# CPLD.net
KiCad netlist of a schematic drawn in Altium Designer
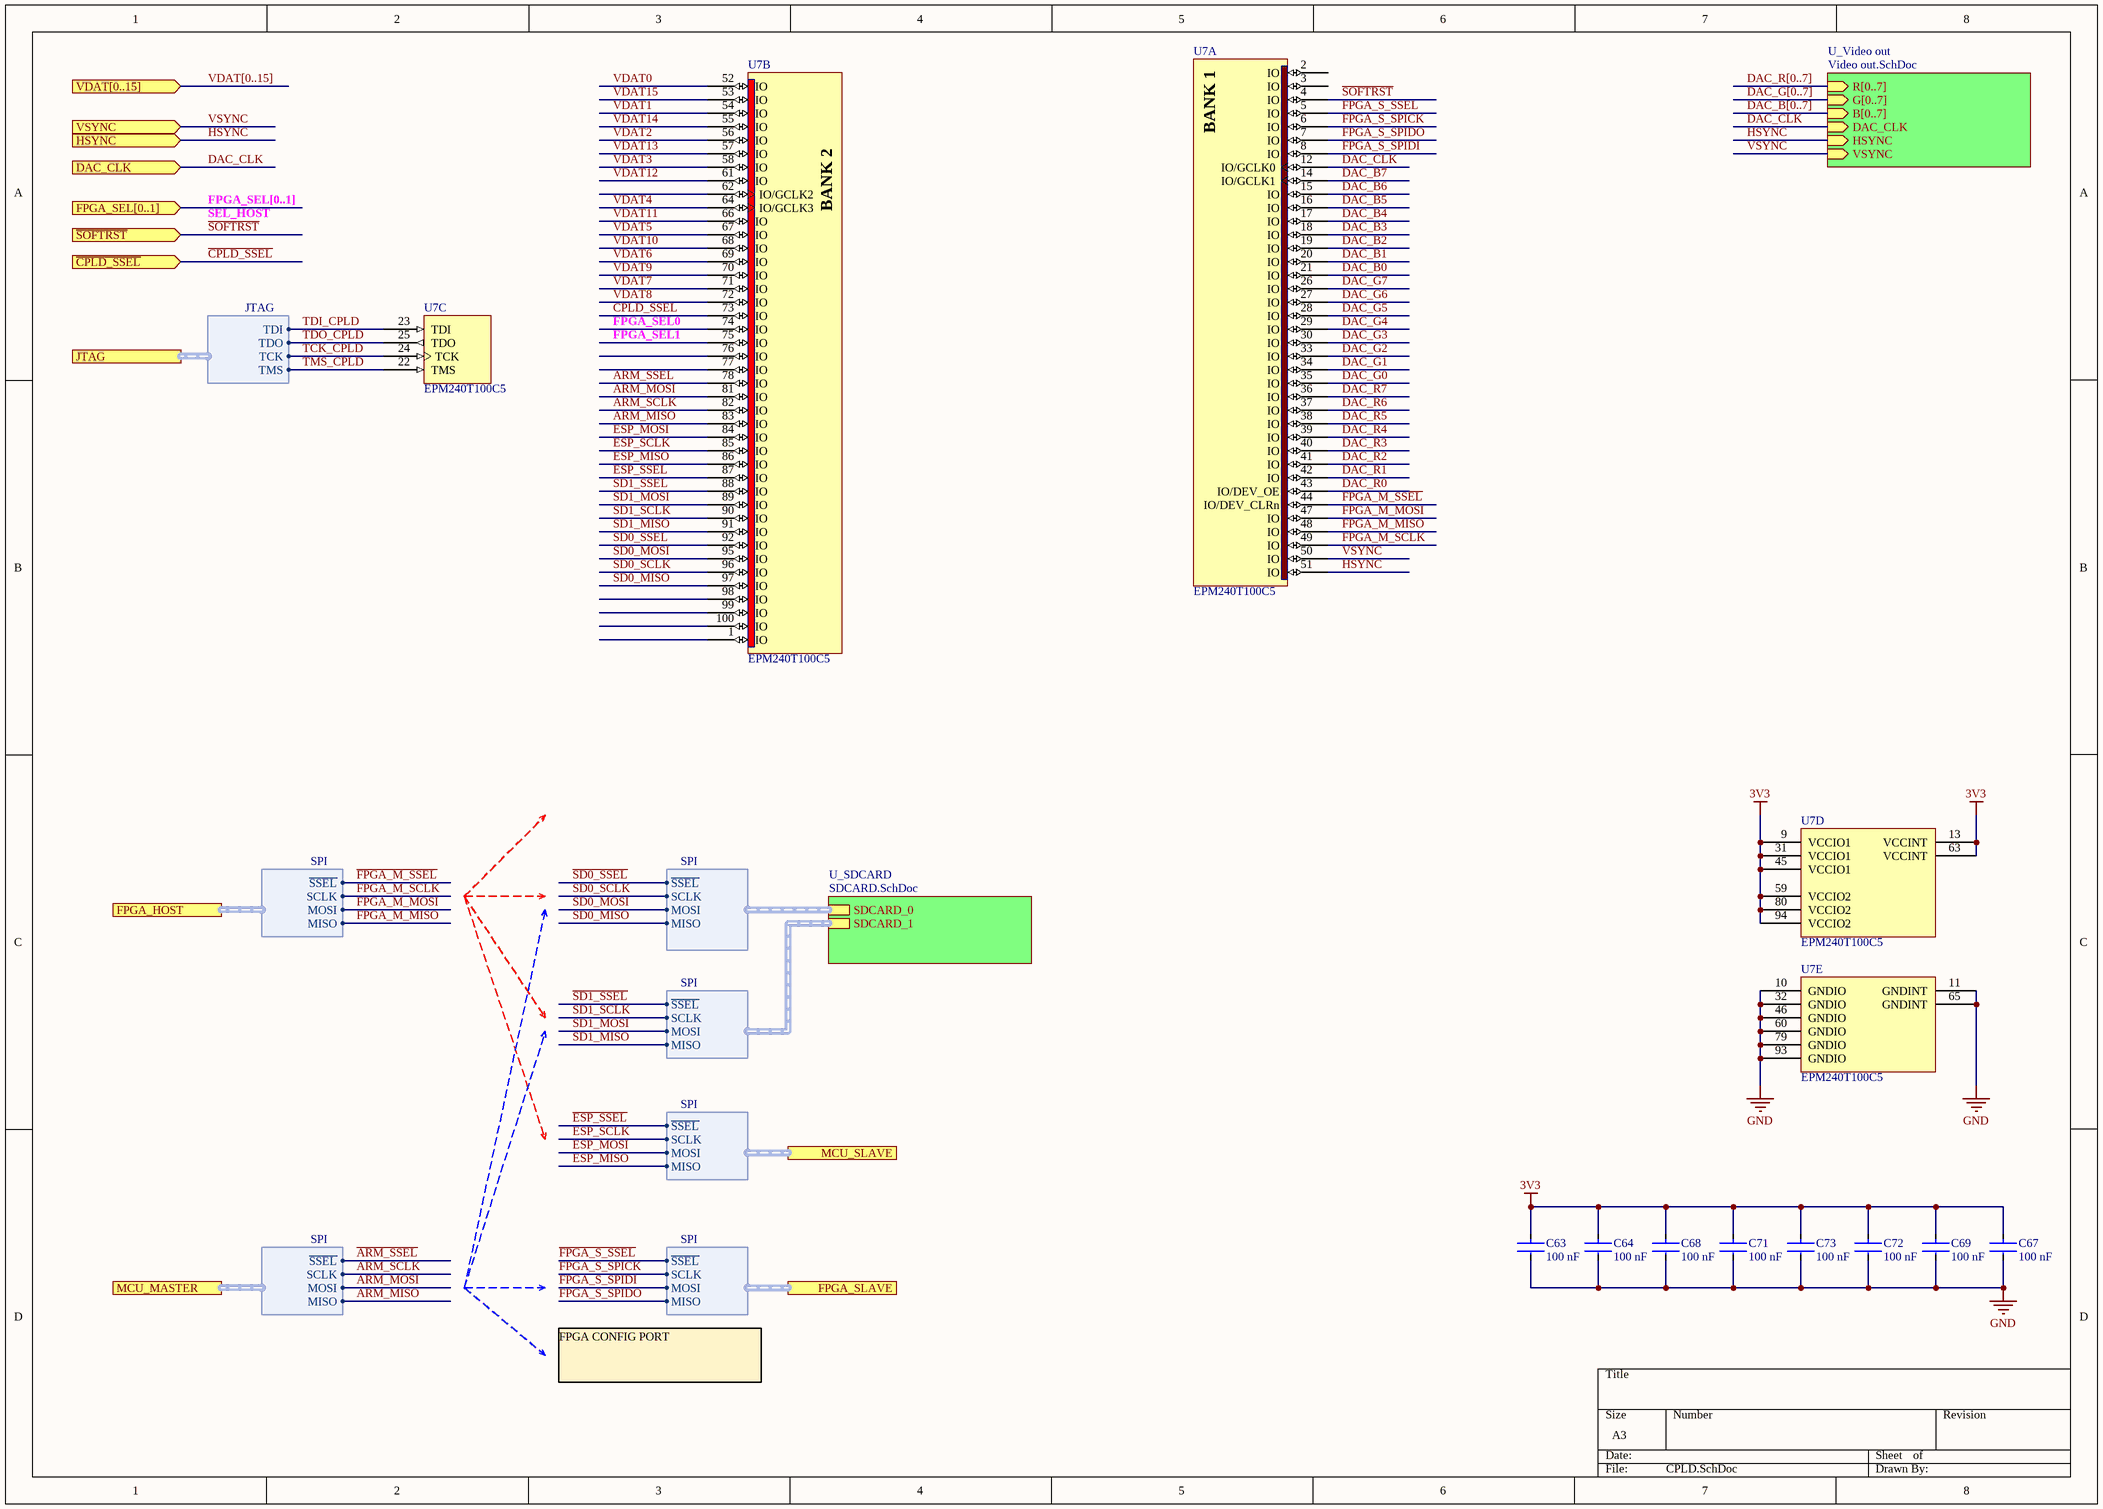
[diagram p0: CPLD.SchDoc]

(export (version "E")
  (design (tool "Eeschema 10.0.6"))
  (components
    (comp (ref "C63")
      (value "CC0805KRX7R9BB104")
      (footprint "FP-CC0805-0_85-IPC_A")
      (description "CAP CER 0.1UF 50V X7R 0805")
      (fields (field (name "MANUFACTURER") "Yageo") (field (name "CAPACITANCE") "100 nF"))
      (libsource (lib "SchLib") (part "CMP-2100-03606-3"))
    )
    (comp (ref "C64")
      (value "CC0805KRX7R9BB104")
      (footprint "FP-CC0805-0_85-IPC_A")
      (description "CAP CER 0.1UF 50V X7R 0805")
      (fields (field (name "MANUFACTURER") "Yageo") (field (name "CAPACITANCE") "100 nF"))
      (libsource (lib "SchLib") (part "CMP-2100-03606-3"))
    )
    (comp (ref "C67")
      (value "CC0805KRX7R9BB104")
      (footprint "FP-CC0805-0_85-IPC_A")
      (description "CAP CER 0.1UF 50V X7R 0805")
      (fields (field (name "MANUFACTURER") "Yageo") (field (name "CAPACITANCE") "100 nF"))
      (libsource (lib "SchLib") (part "CMP-2100-03606-3"))
    )
    (comp (ref "C68")
      (value "CC0805KRX7R9BB104")
      (footprint "FP-CC0805-0_85-IPC_A")
      (description "CAP CER 0.1UF 50V X7R 0805")
      (fields (field (name "MANUFACTURER") "Yageo") (field (name "CAPACITANCE") "100 nF"))
      (libsource (lib "SchLib") (part "CMP-2100-03606-3"))
    )
    (comp (ref "C69")
      (value "CC0805KRX7R9BB104")
      (footprint "FP-CC0805-0_85-IPC_A")
      (description "CAP CER 0.1UF 50V X7R 0805")
      (fields (field (name "MANUFACTURER") "Yageo") (field (name "CAPACITANCE") "100 nF"))
      (libsource (lib "SchLib") (part "CMP-2100-03606-3"))
    )
    (comp (ref "C71")
      (value "CC0805KRX7R9BB104")
      (footprint "FP-CC0805-0_85-IPC_A")
      (description "CAP CER 0.1UF 50V X7R 0805")
      (fields (field (name "MANUFACTURER") "Yageo") (field (name "CAPACITANCE") "100 nF"))
      (libsource (lib "SchLib") (part "CMP-2100-03606-3"))
    )
    (comp (ref "C72")
      (value "CC0805KRX7R9BB104")
      (footprint "FP-CC0805-0_85-IPC_A")
      (description "CAP CER 0.1UF 50V X7R 0805")
      (fields (field (name "MANUFACTURER") "Yageo") (field (name "CAPACITANCE") "100 nF"))
      (libsource (lib "SchLib") (part "CMP-2100-03606-3"))
    )
    (comp (ref "C73")
      (value "CC0805KRX7R9BB104")
      (footprint "FP-CC0805-0_85-IPC_A")
      (description "CAP CER 0.1UF 50V X7R 0805")
      (fields (field (name "MANUFACTURER") "Yageo") (field (name "CAPACITANCE") "100 nF"))
      (libsource (lib "SchLib") (part "CMP-2100-03606-3"))
    )
    (comp (ref "U7")
      (value "EPM240T100C5")
      (footprint "TQFP100_M")
      (fields (field (name "MANUFACTURER") "Intel Altera"))
      (libsource (lib "SchLib") (part "CMP-0144-00216-1"))
    )
  )
  (nets
    (net (code "3") (name "/ARM_MISO") (class "Default")
      (node (ref "U7") (pin "83") (pinfunction "IO_83") (pintype "bidirectional"))
    )
    (net (code "4") (name "/ARM_MOSI") (class "Default")
      (node (ref "U7") (pin "81") (pinfunction "IO_81") (pintype "bidirectional"))
    )
    (net (code "5") (name "/ARM_SCLK") (class "Default")
      (node (ref "U7") (pin "82") (pinfunction "IO_82") (pintype "bidirectional"))
    )
    (net (code "6") (name "/DAC_B0") (class "Default")
      (node (ref "U7") (pin "21") (pinfunction "IO_21") (pintype "bidirectional"))
    )
    (net (code "7") (name "/DAC_B1") (class "Default")
      (node (ref "U7") (pin "20") (pinfunction "IO_20") (pintype "bidirectional"))
    )
    (net (code "8") (name "/DAC_B2") (class "Default")
      (node (ref "U7") (pin "19") (pinfunction "IO_19") (pintype "bidirectional"))
    )
    (net (code "9") (name "/DAC_B3") (class "Default")
      (node (ref "U7") (pin "18") (pinfunction "IO_18") (pintype "bidirectional"))
    )
    (net (code "10") (name "/DAC_B4") (class "Default")
      (node (ref "U7") (pin "17") (pinfunction "IO_17") (pintype "bidirectional"))
    )
    (net (code "11") (name "/DAC_B5") (class "Default")
      (node (ref "U7") (pin "16") (pinfunction "IO_16") (pintype "bidirectional"))
    )
    (net (code "12") (name "/DAC_B6") (class "Default")
      (node (ref "U7") (pin "15") (pinfunction "IO_15") (pintype "bidirectional"))
    )
    (net (code "13") (name "/DAC_B7") (class "Default")
      (node (ref "U7") (pin "14") (pinfunction "IO/GCLK1_14") (pintype "bidirectional"))
    )
    (net (code "15") (name "/DAC_CLK") (class "Default")
      (node (ref "U7") (pin "12") (pinfunction "IO/GCLK0_12") (pintype "bidirectional"))
    )
    (net (code "16") (name "/DAC_G0") (class "Default")
      (node (ref "U7") (pin "35") (pinfunction "IO_35") (pintype "bidirectional"))
    )
    (net (code "17") (name "/DAC_G1") (class "Default")
      (node (ref "U7") (pin "34") (pinfunction "IO_34") (pintype "bidirectional"))
    )
    (net (code "18") (name "/DAC_G2") (class "Default")
      (node (ref "U7") (pin "33") (pinfunction "IO_33") (pintype "bidirectional"))
    )
    (net (code "19") (name "/DAC_G3") (class "Default")
      (node (ref "U7") (pin "30") (pinfunction "IO_30") (pintype "bidirectional"))
    )
    (net (code "20") (name "/DAC_G4") (class "Default")
      (node (ref "U7") (pin "29") (pinfunction "IO_29") (pintype "bidirectional"))
    )
    (net (code "21") (name "/DAC_G5") (class "Default")
      (node (ref "U7") (pin "28") (pinfunction "IO_28") (pintype "bidirectional"))
    )
    (net (code "22") (name "/DAC_G6") (class "Default")
      (node (ref "U7") (pin "27") (pinfunction "IO_27") (pintype "bidirectional"))
    )
    (net (code "23") (name "/DAC_G7") (class "Default")
      (node (ref "U7") (pin "26") (pinfunction "IO_26") (pintype "bidirectional"))
    )
    (net (code "25") (name "/DAC_R0") (class "Default")
      (node (ref "U7") (pin "43") (pinfunction "IO/DEV_OE_43") (pintype "bidirectional"))
    )
    (net (code "26") (name "/DAC_R1") (class "Default")
      (node (ref "U7") (pin "42") (pinfunction "IO_42") (pintype "bidirectional"))
    )
    (net (code "27") (name "/DAC_R2") (class "Default")
      (node (ref "U7") (pin "41") (pinfunction "IO_41") (pintype "bidirectional"))
    )
    (net (code "28") (name "/DAC_R3") (class "Default")
      (node (ref "U7") (pin "40") (pinfunction "IO_40") (pintype "bidirectional"))
    )
    (net (code "29") (name "/DAC_R4") (class "Default")
      (node (ref "U7") (pin "39") (pinfunction "IO_39") (pintype "bidirectional"))
    )
    (net (code "30") (name "/DAC_R5") (class "Default")
      (node (ref "U7") (pin "38") (pinfunction "IO_38") (pintype "bidirectional"))
    )
    (net (code "31") (name "/DAC_R6") (class "Default")
      (node (ref "U7") (pin "37") (pinfunction "IO_37") (pintype "bidirectional"))
    )
    (net (code "32") (name "/DAC_R7") (class "Default")
      (node (ref "U7") (pin "36") (pinfunction "IO_36") (pintype "bidirectional"))
    )
    (net (code "34") (name "/ESP_MISO") (class "Default")
      (node (ref "U7") (pin "86") (pinfunction "IO_86") (pintype "bidirectional"))
    )
    (net (code "35") (name "/ESP_MOSI") (class "Default")
      (node (ref "U7") (pin "84") (pinfunction "IO_84") (pintype "bidirectional"))
    )
    (net (code "36") (name "/ESP_SCLK") (class "Default")
      (node (ref "U7") (pin "85") (pinfunction "IO_85") (pintype "bidirectional"))
    )
    (net (code "37") (name "/FPGA_M_MISO") (class "Default")
      (node (ref "U7") (pin "48") (pinfunction "IO_48") (pintype "bidirectional"))
    )
    (net (code "38") (name "/FPGA_M_MOSI") (class "Default")
      (node (ref "U7") (pin "47") (pinfunction "IO_47") (pintype "bidirectional"))
    )
    (net (code "39") (name "/FPGA_M_SCLK") (class "Default")
      (node (ref "U7") (pin "49") (pinfunction "IO_49") (pintype "bidirectional"))
    )
    (net (code "40") (name "/FPGA_SEL0") (class "Default")
      (node (ref "U7") (pin "74") (pinfunction "IO_74") (pintype "bidirectional"))
    )
    (net (code "41") (name "/FPGA_SEL1") (class "Default")
      (node (ref "U7") (pin "75") (pinfunction "IO_75") (pintype "bidirectional"))
    )
    (net (code "43") (name "/FPGA_S_SPICK") (class "Default")
      (node (ref "U7") (pin "6") (pinfunction "IO_6") (pintype "bidirectional"))
    )
    (net (code "44") (name "/FPGA_S_SPIDI") (class "Default")
      (node (ref "U7") (pin "8") (pinfunction "IO_8") (pintype "bidirectional"))
    )
    (net (code "45") (name "/FPGA_S_SPIDO") (class "Default")
      (node (ref "U7") (pin "7") (pinfunction "IO_7") (pintype "bidirectional"))
    )
    (net (code "46") (name "/HSYNC") (class "Default")
      (node (ref "U7") (pin "51") (pinfunction "IO_51") (pintype "bidirectional"))
    )
    (net (code "47") (name "/SD0_MISO") (class "Default")
      (node (ref "U7") (pin "97") (pinfunction "IO_97") (pintype "bidirectional"))
    )
    (net (code "48") (name "/SD0_MOSI") (class "Default")
      (node (ref "U7") (pin "95") (pinfunction "IO_95") (pintype "bidirectional"))
    )
    (net (code "49") (name "/SD0_SCLK") (class "Default")
      (node (ref "U7") (pin "96") (pinfunction "IO_96") (pintype "bidirectional"))
    )
    (net (code "50") (name "/SD1_MISO") (class "Default")
      (node (ref "U7") (pin "91") (pinfunction "IO_91") (pintype "bidirectional"))
    )
    (net (code "51") (name "/SD1_MOSI") (class "Default")
      (node (ref "U7") (pin "89") (pinfunction "IO_89") (pintype "bidirectional"))
    )
    (net (code "52") (name "/SD1_SCLK") (class "Default")
      (node (ref "U7") (pin "90") (pinfunction "IO_90") (pintype "bidirectional"))
    )
    (net (code "54") (name "/TCK_CPLD") (class "Default")
      (node (ref "U7") (pin "24") (pinfunction "TCK_24") (pintype "input"))
    )
    (net (code "55") (name "/TDI_CPLD") (class "Default")
      (node (ref "U7") (pin "23") (pinfunction "TDI_23") (pintype "input"))
    )
    (net (code "56") (name "/TDO_CPLD") (class "Default")
      (node (ref "U7") (pin "25") (pinfunction "TDO_25") (pintype "output"))
    )
    (net (code "57") (name "/TMS_CPLD") (class "Default")
      (node (ref "U7") (pin "22") (pinfunction "TMS_22") (pintype "input"))
    )
    (net (code "58") (name "/VDAT0") (class "Default")
      (node (ref "U7") (pin "52") (pinfunction "IO_52") (pintype "bidirectional"))
    )
    (net (code "59") (name "/VDAT1") (class "Default")
      (node (ref "U7") (pin "54") (pinfunction "IO_54") (pintype "bidirectional"))
    )
    (net (code "60") (name "/VDAT2") (class "Default")
      (node (ref "U7") (pin "56") (pinfunction "IO_56") (pintype "bidirectional"))
    )
    (net (code "61") (name "/VDAT3") (class "Default")
      (node (ref "U7") (pin "58") (pinfunction "IO_58") (pintype "bidirectional"))
    )
    (net (code "62") (name "/VDAT4") (class "Default")
      (node (ref "U7") (pin "64") (pinfunction "IO/GCLK3_64") (pintype "bidirectional"))
    )
    (net (code "63") (name "/VDAT5") (class "Default")
      (node (ref "U7") (pin "67") (pinfunction "IO_67") (pintype "bidirectional"))
    )
    (net (code "64") (name "/VDAT6") (class "Default")
      (node (ref "U7") (pin "69") (pinfunction "IO_69") (pintype "bidirectional"))
    )
    (net (code "65") (name "/VDAT7") (class "Default")
      (node (ref "U7") (pin "71") (pinfunction "IO_71") (pintype "bidirectional"))
    )
    (net (code "66") (name "/VDAT8") (class "Default")
      (node (ref "U7") (pin "72") (pinfunction "IO_72") (pintype "bidirectional"))
    )
    (net (code "67") (name "/VDAT9") (class "Default")
      (node (ref "U7") (pin "70") (pinfunction "IO_70") (pintype "bidirectional"))
    )
    (net (code "68") (name "/VDAT10") (class "Default")
      (node (ref "U7") (pin "68") (pinfunction "IO_68") (pintype "bidirectional"))
    )
    (net (code "69") (name "/VDAT11") (class "Default")
      (node (ref "U7") (pin "66") (pinfunction "IO_66") (pintype "bidirectional"))
    )
    (net (code "70") (name "/VDAT12") (class "Default")
      (node (ref "U7") (pin "61") (pinfunction "IO_61") (pintype "bidirectional"))
    )
    (net (code "71") (name "/VDAT13") (class "Default")
      (node (ref "U7") (pin "57") (pinfunction "IO_57") (pintype "bidirectional"))
    )
    (net (code "72") (name "/VDAT14") (class "Default")
      (node (ref "U7") (pin "55") (pinfunction "IO_55") (pintype "bidirectional"))
    )
    (net (code "73") (name "/VDAT15") (class "Default")
      (node (ref "U7") (pin "53") (pinfunction "IO_53") (pintype "bidirectional"))
    )
    (net (code "75") (name "/VSYNC") (class "Default")
      (node (ref "U7") (pin "50") (pinfunction "IO_50") (pintype "bidirectional"))
    )
    (net (code "78") (name "/~{ARM_SSEL}") (class "Default")
      (node (ref "U7") (pin "78") (pinfunction "IO_78") (pintype "bidirectional"))
    )
    (net (code "79") (name "/~{CPLD_SSEL}") (class "Default")
      (node (ref "U7") (pin "73") (pinfunction "IO_73") (pintype "bidirectional"))
    )
    (net (code "80") (name "/~{ESP_SSEL}") (class "Default")
      (node (ref "U7") (pin "87") (pinfunction "IO_87") (pintype "bidirectional"))
    )
    (net (code "81") (name "/~{FPGA_M_SSEL}") (class "Default")
      (node (ref "U7") (pin "44") (pinfunction "IO/DEV_CLRn_44") (pintype "bidirectional"))
    )
    (net (code "82") (name "/~{FPGA_S_SSEL}") (class "Default")
      (node (ref "U7") (pin "5") (pinfunction "IO_5") (pintype "bidirectional"))
    )
    (net (code "83") (name "/~{SD0_SSEL}") (class "Default")
      (node (ref "U7") (pin "92") (pinfunction "IO_92") (pintype "bidirectional"))
    )
    (net (code "84") (name "/~{SD1_SSEL}") (class "Default")
      (node (ref "U7") (pin "88") (pinfunction "IO_88") (pintype "bidirectional"))
    )
    (net (code "85") (name "/~{SOFTRST}") (class "Default")
      (node (ref "U7") (pin "4") (pinfunction "IO_4") (pintype "bidirectional"))
    )
    (net (code "86") (name "3V3") (class "Default")
      (node (ref "C63") (pin "1") (pinfunction "1_1") (pintype "passive"))
      (node (ref "C64") (pin "1") (pinfunction "1_1") (pintype "passive"))
      (node (ref "C67") (pin "1") (pinfunction "1_1") (pintype "passive"))
      (node (ref "C68") (pin "1") (pinfunction "1_1") (pintype "passive"))
      (node (ref "C69") (pin "1") (pinfunction "1_1") (pintype "passive"))
      (node (ref "C71") (pin "1") (pinfunction "1_1") (pintype "passive"))
      (node (ref "C72") (pin "1") (pinfunction "1_1") (pintype "passive"))
      (node (ref "C73") (pin "1") (pinfunction "1_1") (pintype "passive"))
      (node (ref "U7") (pin "13") (pinfunction "VCCINT_13") (pintype "power_in"))
      (node (ref "U7") (pin "31") (pinfunction "VCCIO1_31") (pintype "power_in"))
      (node (ref "U7") (pin "45") (pinfunction "VCCIO1_45") (pintype "power_in"))
      (node (ref "U7") (pin "59") (pinfunction "VCCIO2_59") (pintype "power_in"))
      (node (ref "U7") (pin "63") (pinfunction "VCCINT_63") (pintype "power_in"))
      (node (ref "U7") (pin "80") (pinfunction "VCCIO2_80") (pintype "power_in"))
      (node (ref "U7") (pin "9") (pinfunction "VCCIO1_9") (pintype "power_in"))
      (node (ref "U7") (pin "94") (pinfunction "VCCIO2_94") (pintype "power_in"))
    )
    (net (code "87") (name "GND") (class "Default")
      (node (ref "C63") (pin "2") (pinfunction "2_2") (pintype "passive"))
      (node (ref "C64") (pin "2") (pinfunction "2_2") (pintype "passive"))
      (node (ref "C67") (pin "2") (pinfunction "2_2") (pintype "passive"))
      (node (ref "C68") (pin "2") (pinfunction "2_2") (pintype "passive"))
      (node (ref "C69") (pin "2") (pinfunction "2_2") (pintype "passive"))
      (node (ref "C71") (pin "2") (pinfunction "2_2") (pintype "passive"))
      (node (ref "C72") (pin "2") (pinfunction "2_2") (pintype "passive"))
      (node (ref "C73") (pin "2") (pinfunction "2_2") (pintype "passive"))
      (node (ref "U7") (pin "10") (pinfunction "GNDIO_10") (pintype "power_in"))
      (node (ref "U7") (pin "11") (pinfunction "GNDINT_11") (pintype "power_in"))
      (node (ref "U7") (pin "32") (pinfunction "GNDIO_32") (pintype "power_in"))
      (node (ref "U7") (pin "46") (pinfunction "GNDIO_46") (pintype "power_in"))
      (node (ref "U7") (pin "60") (pinfunction "GNDIO_60") (pintype "power_in"))
      (node (ref "U7") (pin "65") (pinfunction "GNDINT_65") (pintype "power_in"))
      (node (ref "U7") (pin "79") (pinfunction "GNDIO_79") (pintype "power_in"))
      (node (ref "U7") (pin "93") (pinfunction "GNDIO_93") (pintype "power_in"))
    )
    (net (code "88") (name "unconnected-(U7A-IO-Pad2)") (class "Default")
      (node (ref "U7") (pin "2") (pinfunction "IO_2") (pintype "bidirectional"))
    )
    (net (code "89") (name "unconnected-(U7A-IO-Pad3)") (class "Default")
      (node (ref "U7") (pin "3") (pinfunction "IO_3") (pintype "bidirectional"))
    )
    (net (code "90") (name "unconnected-(U7B-IO-Pad1)") (class "Default")
      (node (ref "U7") (pin "1") (pinfunction "IO_1") (pintype "bidirectional"))
    )
    (net (code "91") (name "unconnected-(U7B-IO-Pad76)") (class "Default")
      (node (ref "U7") (pin "76") (pinfunction "IO_76") (pintype "bidirectional"))
    )
    (net (code "92") (name "unconnected-(U7B-IO-Pad77)") (class "Default")
      (node (ref "U7") (pin "77") (pinfunction "IO_77") (pintype "bidirectional"))
    )
    (net (code "93") (name "unconnected-(U7B-IO-Pad98)") (class "Default")
      (node (ref "U7") (pin "98") (pinfunction "IO_98") (pintype "bidirectional"))
    )
    (net (code "94") (name "unconnected-(U7B-IO-Pad99)") (class "Default")
      (node (ref "U7") (pin "99") (pinfunction "IO_99") (pintype "bidirectional"))
    )
    (net (code "95") (name "unconnected-(U7B-IO-Pad100)") (class "Default")
      (node (ref "U7") (pin "100") (pinfunction "IO_100") (pintype "bidirectional"))
    )
    (net (code "96") (name "unconnected-(U7B-IO{slash}GCLK2-Pad62)") (class "Default")
      (node (ref "U7") (pin "62") (pinfunction "IO/GCLK2_62") (pintype "bidirectional"))
    )
  )
)
